# fngAfro.net
KiCad netlist of a schematic drawn in EAGLE
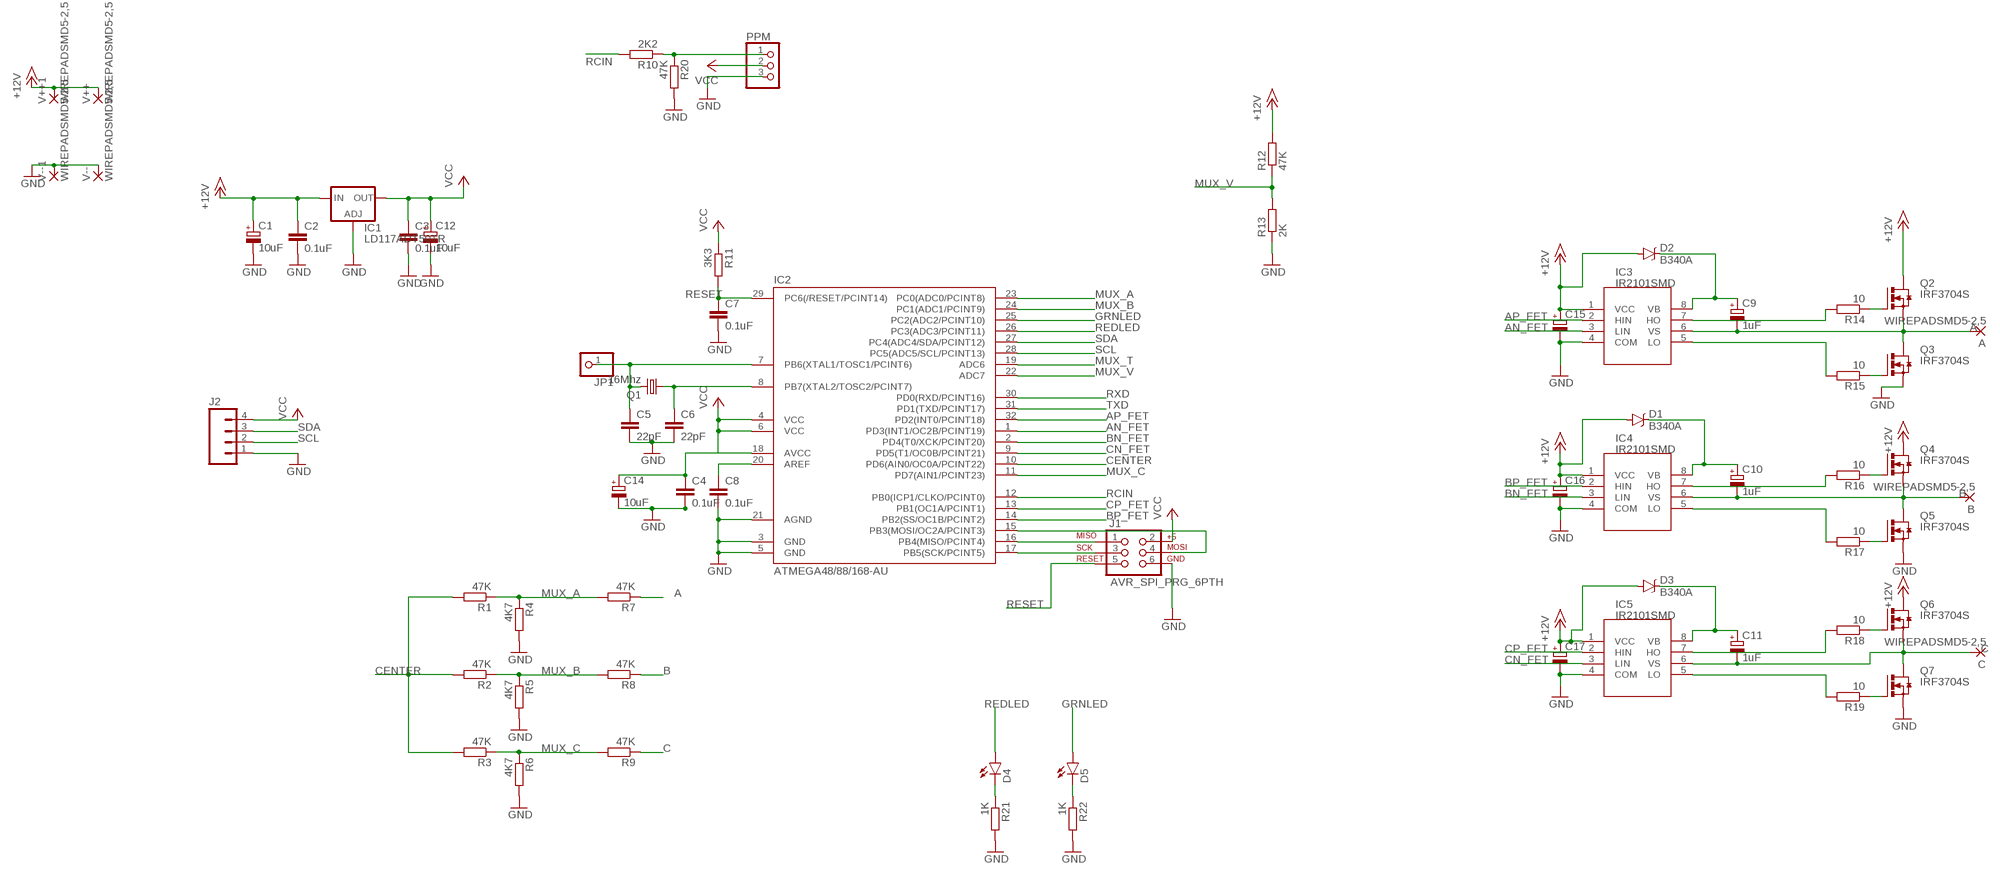
[diagram p0: schematic, sheet 1]

(export (version "E")
  (design (tool "Eeschema 10.0.6"))
  (components
    (comp (ref "A")
      (value "WIREPADSMD5-2,5")
      (footprint "eagle-import:5-2,5")
      (libsource (lib "eagle-import") (part "WIREPADSMD5-2,5"))
    )
    (comp (ref "B")
      (value "WIREPADSMD5-2,5")
      (footprint "eagle-import:5-2,5")
      (libsource (lib "eagle-import") (part "WIREPADSMD5-2,5"))
    )
    (comp (ref "C")
      (value "WIREPADSMD5-2,5")
      (footprint "eagle-import:5-2,5")
      (libsource (lib "eagle-import") (part "WIREPADSMD5-2,5"))
    )
    (comp (ref "C1")
      (value "10uF")
      (footprint "eagle-import:CT3216")
      (libsource (lib "eagle-import") (part "CPOL-EUCT3216"))
    )
    (comp (ref "C2")
      (value "0.1uF")
      (footprint "eagle-import:C1206K")
      (libsource (lib "eagle-import") (part "C-EUC1206K"))
    )
    (comp (ref "C3")
      (value "0.1uF")
      (footprint "eagle-import:C1206K")
      (libsource (lib "eagle-import") (part "C-EUC1206K"))
    )
    (comp (ref "C4")
      (value "0.1uF")
      (footprint "eagle-import:C1206K")
      (libsource (lib "eagle-import") (part "C-EUC1206K"))
    )
    (comp (ref "C5")
      (value "22pF")
      (footprint "eagle-import:C1206K")
      (libsource (lib "eagle-import") (part "C-EUC1206K"))
    )
    (comp (ref "C6")
      (value "22pF")
      (footprint "eagle-import:C1206K")
      (libsource (lib "eagle-import") (part "C-EUC1206K"))
    )
    (comp (ref "C7")
      (value "0.1uF")
      (footprint "eagle-import:C1206K")
      (libsource (lib "eagle-import") (part "C-EUC1206K"))
    )
    (comp (ref "C8")
      (value "0.1uF")
      (footprint "eagle-import:C1206K")
      (libsource (lib "eagle-import") (part "C-EUC1206K"))
    )
    (comp (ref "C9")
      (value "1uF")
      (footprint "eagle-import:B_3528-21R")
      (libsource (lib "eagle-import") (part "CPOL-EUB/3528-21R"))
    )
    (comp (ref "C10")
      (value "1uF")
      (footprint "eagle-import:B_3528-21R")
      (libsource (lib "eagle-import") (part "CPOL-EUB/3528-21R"))
    )
    (comp (ref "C11")
      (value "1uF")
      (footprint "eagle-import:B_3528-21R")
      (libsource (lib "eagle-import") (part "CPOL-EUB/3528-21R"))
    )
    (comp (ref "C12")
      (value "10uF")
      (footprint "eagle-import:A_3216-18W")
      (libsource (lib "eagle-import") (part "CPOL-EUA/3216-18W"))
    )
    (comp (ref "C14")
      (value "10uF")
      (footprint "eagle-import:A_3216-18W")
      (libsource (lib "eagle-import") (part "CPOL-EUA/3216-18W"))
    )
    (comp (ref "C15")
      (value "CPOL-EUA/3216-18W")
      (footprint "eagle-import:A_3216-18W")
      (libsource (lib "eagle-import") (part "CPOL-EUA/3216-18W"))
    )
    (comp (ref "C16")
      (value "CPOL-EUA/3216-18W")
      (footprint "eagle-import:A_3216-18W")
      (libsource (lib "eagle-import") (part "CPOL-EUA/3216-18W"))
    )
    (comp (ref "C17")
      (value "CPOL-EUA/3216-18W")
      (footprint "eagle-import:A_3216-18W")
      (libsource (lib "eagle-import") (part "CPOL-EUA/3216-18W"))
    )
    (comp (ref "D1")
      (value "B340A")
      (footprint "eagle-import:SMA-DIODE")
      (libsource (lib "eagle-import") (part "DIODE-SCHOTTKY-B340A"))
    )
    (comp (ref "D2")
      (value "B340A")
      (footprint "eagle-import:SMA-DIODE")
      (libsource (lib "eagle-import") (part "DIODE-SCHOTTKY-B340A"))
    )
    (comp (ref "D3")
      (value "B340A")
      (footprint "eagle-import:SMA-DIODE")
      (libsource (lib "eagle-import") (part "DIODE-SCHOTTKY-B340A"))
    )
    (comp (ref "D4")
      (value "LED-FKIT-1206")
      (footprint "eagle-import:FKIT-LED-1206")
      (libsource (lib "eagle-import") (part "LED-FKIT-1206"))
    )
    (comp (ref "D5")
      (value "LED-FKIT-1206")
      (footprint "eagle-import:FKIT-LED-1206")
      (libsource (lib "eagle-import") (part "LED-FKIT-1206"))
    )
    (comp (ref "IC1")
      (value "LD117ADT50TR")
      (footprint "eagle-import:DPACK")
      (libsource (lib "eagle-import") (part "LD117A?DT50TR"))
    )
    (comp (ref "IC2")
      (value "ATMEGA48/88/168-AU")
      (footprint "eagle-import:TQFP32-08")
      (libsource (lib "eagle-import") (part "ATMEGA48/88/168-AU"))
    )
    (comp (ref "IC3")
      (value "IR2101SMD")
      (footprint "eagle-import:SO08")
      (libsource (lib "eagle-import") (part "IR2101SMD"))
    )
    (comp (ref "IC4")
      (value "IR2101SMD")
      (footprint "eagle-import:SO08")
      (libsource (lib "eagle-import") (part "IR2101SMD"))
    )
    (comp (ref "IC5")
      (value "IR2101SMD")
      (footprint "eagle-import:SO08")
      (libsource (lib "eagle-import") (part "IR2101SMD"))
    )
    (comp (ref "J1")
      (value "AVR_SPI_PRG_6PTH")
      (footprint "eagle-import:2X3")
      (libsource (lib "eagle-import") (part "AVR_SPI_PRG_6PTH"))
    )
    (comp (ref "J2")
      (value "M04LOCK")
      (footprint "eagle-import:1X04_LOCK")
      (libsource (lib "eagle-import") (part "M04LOCK"))
    )
    (comp (ref "JP1")
      (value "PINHD-1X1")
      (footprint "eagle-import:1X01")
      (libsource (lib "eagle-import") (part "PINHD-1X1"))
    )
    (comp (ref "PPM")
      (value "PINHD-1X3/90")
      (footprint "eagle-import:1X03_90")
      (libsource (lib "eagle-import") (part "PINHD-1X3/90"))
    )
    (comp (ref "Q1")
      (value "16Mhz")
      (footprint "eagle-import:HC49U70")
      (libsource (lib "eagle-import") (part "CRYSTALHC49U70"))
    )
    (comp (ref "Q2")
      (value "IRF3704S")
      (footprint "eagle-import:D2PACK")
      (libsource (lib "eagle-import") (part "IRF3704S"))
    )
    (comp (ref "Q3")
      (value "IRF3704S")
      (footprint "eagle-import:D2PACK")
      (libsource (lib "eagle-import") (part "IRF3704S"))
    )
    (comp (ref "Q4")
      (value "IRF3704S")
      (footprint "eagle-import:D2PACK")
      (libsource (lib "eagle-import") (part "IRF3704S"))
    )
    (comp (ref "Q5")
      (value "IRF3704S")
      (footprint "eagle-import:D2PACK")
      (libsource (lib "eagle-import") (part "IRF3704S"))
    )
    (comp (ref "Q6")
      (value "IRF3704S")
      (footprint "eagle-import:D2PACK")
      (libsource (lib "eagle-import") (part "IRF3704S"))
    )
    (comp (ref "Q7")
      (value "IRF3704S")
      (footprint "eagle-import:D2PACK")
      (libsource (lib "eagle-import") (part "IRF3704S"))
    )
    (comp (ref "R1")
      (value "47K")
      (footprint "eagle-import:M0805")
      (libsource (lib "eagle-import") (part "R-EU_M0805"))
    )
    (comp (ref "R2")
      (value "47K")
      (footprint "eagle-import:M0805")
      (libsource (lib "eagle-import") (part "R-EU_M0805"))
    )
    (comp (ref "R3")
      (value "47K")
      (footprint "eagle-import:M0805")
      (libsource (lib "eagle-import") (part "R-EU_M0805"))
    )
    (comp (ref "R4")
      (value "4K7")
      (footprint "eagle-import:M0805")
      (libsource (lib "eagle-import") (part "R-EU_M0805"))
    )
    (comp (ref "R5")
      (value "4K7")
      (footprint "eagle-import:M0805")
      (libsource (lib "eagle-import") (part "R-EU_M0805"))
    )
    (comp (ref "R6")
      (value "4K7")
      (footprint "eagle-import:M0805")
      (libsource (lib "eagle-import") (part "R-EU_M0805"))
    )
    (comp (ref "R7")
      (value "47K")
      (footprint "eagle-import:M0805")
      (libsource (lib "eagle-import") (part "R-EU_M0805"))
    )
    (comp (ref "R8")
      (value "47K")
      (footprint "eagle-import:M0805")
      (libsource (lib "eagle-import") (part "R-EU_M0805"))
    )
    (comp (ref "R9")
      (value "47K")
      (footprint "eagle-import:M0805")
      (libsource (lib "eagle-import") (part "R-EU_M0805"))
    )
    (comp (ref "R10")
      (value "2K2")
      (footprint "eagle-import:M1206")
      (libsource (lib "eagle-import") (part "R-EU_M1206"))
    )
    (comp (ref "R11")
      (value "3K3")
      (footprint "eagle-import:M1206")
      (libsource (lib "eagle-import") (part "R-EU_M1206"))
    )
    (comp (ref "R12")
      (value "47K")
      (footprint "eagle-import:M0805")
      (libsource (lib "eagle-import") (part "R-EU_M0805"))
    )
    (comp (ref "R13")
      (value "2K")
      (footprint "eagle-import:M0805")
      (libsource (lib "eagle-import") (part "R-EU_M0805"))
    )
    (comp (ref "R14")
      (value "10")
      (footprint "eagle-import:M0805")
      (libsource (lib "eagle-import") (part "R-EU_M0805"))
    )
    (comp (ref "R15")
      (value "10")
      (footprint "eagle-import:M0805")
      (libsource (lib "eagle-import") (part "R-EU_M0805"))
    )
    (comp (ref "R16")
      (value "10")
      (footprint "eagle-import:M0805")
      (libsource (lib "eagle-import") (part "R-EU_M0805"))
    )
    (comp (ref "R17")
      (value "10")
      (footprint "eagle-import:M0805")
      (libsource (lib "eagle-import") (part "R-EU_M0805"))
    )
    (comp (ref "R18")
      (value "10")
      (footprint "eagle-import:M0805")
      (libsource (lib "eagle-import") (part "R-EU_M0805"))
    )
    (comp (ref "R19")
      (value "10")
      (footprint "eagle-import:M0805")
      (libsource (lib "eagle-import") (part "R-EU_M0805"))
    )
    (comp (ref "R20")
      (value "47K")
      (footprint "eagle-import:M1206")
      (libsource (lib "eagle-import") (part "R-EU_M1206"))
    )
    (comp (ref "R21")
      (value "1K")
      (footprint "eagle-import:M0805")
      (libsource (lib "eagle-import") (part "R-EU_M0805"))
    )
    (comp (ref "R22")
      (value "1K")
      (footprint "eagle-import:M0805")
      (libsource (lib "eagle-import") (part "R-EU_M0805"))
    )
    (comp (ref "V++")
      (value "WIREPADSMD5-2,5")
      (footprint "eagle-import:5-2,5")
      (libsource (lib "eagle-import") (part "WIREPADSMD5-2,5"))
    )
    (comp (ref "V++1")
      (value "WIREPADSMD5-2,5")
      (footprint "eagle-import:5-2,5")
      (libsource (lib "eagle-import") (part "WIREPADSMD5-2,5"))
    )
    (comp (ref "V--")
      (value "WIREPADSMD5-2,5")
      (footprint "eagle-import:5-2,5")
      (libsource (lib "eagle-import") (part "WIREPADSMD5-2,5"))
    )
    (comp (ref "V--1")
      (value "WIREPADSMD5-2,5")
      (footprint "eagle-import:5-2,5")
      (libsource (lib "eagle-import") (part "WIREPADSMD5-2,5"))
    )
  )
  (nets
    (net (code "1") (name "+12V") (class "Default")
      (node (ref "C1") (pin "+") (pinfunction "+_+") (pintype "passive"))
      (node (ref "C15") (pin "+") (pinfunction "+_+") (pintype "passive"))
      (node (ref "C16") (pin "+") (pinfunction "+_+") (pintype "passive"))
      (node (ref "C17") (pin "+") (pinfunction "+_+") (pintype "passive"))
      (node (ref "C2") (pin "1") (pinfunction "1_1") (pintype "passive"))
      (node (ref "D1") (pin "A") (pinfunction "A_A") (pintype "passive"))
      (node (ref "D2") (pin "A") (pinfunction "A_A") (pintype "passive"))
      (node (ref "D3") (pin "A") (pinfunction "A_A") (pintype "passive"))
      (node (ref "IC1") (pin "3") (pinfunction "IN_3") (pintype "input"))
      (node (ref "IC3") (pin "1") (pinfunction "VCC_1") (pintype "bidirectional"))
      (node (ref "IC4") (pin "1") (pinfunction "VCC_1") (pintype "bidirectional"))
      (node (ref "IC5") (pin "1") (pinfunction "VCC_1") (pintype "bidirectional"))
      (node (ref "Q2") (pin "2") (pinfunction "D_2") (pintype "passive"))
      (node (ref "Q4") (pin "2") (pinfunction "D_2") (pintype "passive"))
      (node (ref "Q6") (pin "2") (pinfunction "D_2") (pintype "passive"))
      (node (ref "R12") (pin "2") (pinfunction "2_2") (pintype "passive"))
      (node (ref "V++") (pin "1") (pinfunction "P_1") (pintype "passive"))
      (node (ref "V++1") (pin "1") (pinfunction "P_1") (pintype "passive"))
    )
    (net (code "2") (name "/A") (class "Default")
      (node (ref "A") (pin "1") (pinfunction "P_1") (pintype "passive"))
      (node (ref "C9") (pin "-") (pinfunction "-_-") (pintype "passive"))
      (node (ref "IC3") (pin "6") (pinfunction "VS_6") (pintype "bidirectional"))
      (node (ref "Q2") (pin "3") (pinfunction "S_3") (pintype "passive"))
      (node (ref "Q3") (pin "2") (pinfunction "D_2") (pintype "passive"))
      (node (ref "R7") (pin "1") (pinfunction "1_1") (pintype "passive"))
    )
    (net (code "3") (name "/AN_FET") (class "Default")
      (node (ref "IC2") (pin "1") (pinfunction "PD3(INT1/OC2B/PCINT19)_1") (pintype "bidirectional"))
      (node (ref "IC3") (pin "3") (pinfunction "LIN_3") (pintype "bidirectional"))
    )
    (net (code "4") (name "/AP_FET") (class "Default")
      (node (ref "IC2") (pin "32") (pinfunction "PD2(INT0/PCINT18)_32") (pintype "bidirectional"))
      (node (ref "IC3") (pin "2") (pinfunction "HIN_2") (pintype "bidirectional"))
    )
    (net (code "5") (name "/B") (class "Default")
      (node (ref "B") (pin "1") (pinfunction "P_1") (pintype "passive"))
      (node (ref "C10") (pin "-") (pinfunction "-_-") (pintype "passive"))
      (node (ref "IC4") (pin "6") (pinfunction "VS_6") (pintype "bidirectional"))
      (node (ref "Q4") (pin "3") (pinfunction "S_3") (pintype "passive"))
      (node (ref "Q5") (pin "2") (pinfunction "D_2") (pintype "passive"))
      (node (ref "R8") (pin "1") (pinfunction "1_1") (pintype "passive"))
    )
    (net (code "6") (name "/BN_FET") (class "Default")
      (node (ref "IC2") (pin "2") (pinfunction "PD4(T0/XCK/PCINT20)_2") (pintype "bidirectional"))
      (node (ref "IC4") (pin "3") (pinfunction "LIN_3") (pintype "bidirectional"))
    )
    (net (code "7") (name "/BP_FET") (class "Default")
      (node (ref "IC2") (pin "14") (pinfunction "PB2(SS/OC1B/PCINT2)_14") (pintype "bidirectional"))
      (node (ref "IC4") (pin "2") (pinfunction "HIN_2") (pintype "bidirectional"))
    )
    (net (code "8") (name "/C") (class "Default")
      (node (ref "C") (pin "1") (pinfunction "P_1") (pintype "passive"))
      (node (ref "C11") (pin "-") (pinfunction "-_-") (pintype "passive"))
      (node (ref "IC5") (pin "6") (pinfunction "VS_6") (pintype "bidirectional"))
      (node (ref "Q6") (pin "3") (pinfunction "S_3") (pintype "passive"))
      (node (ref "Q7") (pin "2") (pinfunction "D_2") (pintype "passive"))
      (node (ref "R9") (pin "1") (pinfunction "1_1") (pintype "passive"))
    )
    (net (code "9") (name "/CENTER") (class "Default")
      (node (ref "IC2") (pin "10") (pinfunction "PD6(AIN0/OC0A/PCINT22)_10") (pintype "bidirectional"))
      (node (ref "R1") (pin "2") (pinfunction "2_2") (pintype "passive"))
      (node (ref "R2") (pin "2") (pinfunction "2_2") (pintype "passive"))
      (node (ref "R3") (pin "2") (pinfunction "2_2") (pintype "passive"))
    )
    (net (code "10") (name "/CN_FET") (class "Default")
      (node (ref "IC2") (pin "9") (pinfunction "PD5(T1/OC0B/PCINT21)_9") (pintype "bidirectional"))
      (node (ref "IC5") (pin "3") (pinfunction "LIN_3") (pintype "bidirectional"))
    )
    (net (code "11") (name "/CP_FET") (class "Default")
      (node (ref "IC2") (pin "13") (pinfunction "PB1(OC1A/PCINT1)_13") (pintype "bidirectional"))
      (node (ref "IC5") (pin "2") (pinfunction "HIN_2") (pintype "bidirectional"))
    )
    (net (code "12") (name "/GRNLED") (class "Default")
      (node (ref "D5") (pin "A") (pinfunction "A_A") (pintype "passive"))
      (node (ref "IC2") (pin "25") (pinfunction "PC2(ADC2/PCINT10)_25") (pintype "bidirectional"))
    )
    (net (code "13") (name "/MUX_A") (class "Default")
      (node (ref "IC2") (pin "23") (pinfunction "PC0(ADC0/PCINT8)_23") (pintype "bidirectional"))
      (node (ref "R1") (pin "1") (pinfunction "1_1") (pintype "passive"))
      (node (ref "R4") (pin "1") (pinfunction "1_1") (pintype "passive"))
      (node (ref "R7") (pin "2") (pinfunction "2_2") (pintype "passive"))
    )
    (net (code "14") (name "/MUX_B") (class "Default")
      (node (ref "IC2") (pin "24") (pinfunction "PC1(ADC1/PCINT9)_24") (pintype "bidirectional"))
      (node (ref "R2") (pin "1") (pinfunction "1_1") (pintype "passive"))
      (node (ref "R5") (pin "1") (pinfunction "1_1") (pintype "passive"))
      (node (ref "R8") (pin "2") (pinfunction "2_2") (pintype "passive"))
    )
    (net (code "15") (name "/MUX_C") (class "Default")
      (node (ref "IC2") (pin "11") (pinfunction "PD7(AIN1/PCINT23)_11") (pintype "bidirectional"))
      (node (ref "R3") (pin "1") (pinfunction "1_1") (pintype "passive"))
      (node (ref "R6") (pin "1") (pinfunction "1_1") (pintype "passive"))
      (node (ref "R9") (pin "2") (pinfunction "2_2") (pintype "passive"))
    )
    (net (code "16") (name "/MUX_T") (class "Default")
      (node (ref "IC2") (pin "19") (pinfunction "ADC6_19") (pintype "passive"))
    )
    (net (code "17") (name "/MUX_V") (class "Default")
      (node (ref "IC2") (pin "22") (pinfunction "ADC7_22") (pintype "passive"))
      (node (ref "R12") (pin "1") (pinfunction "1_1") (pintype "passive"))
      (node (ref "R13") (pin "2") (pinfunction "2_2") (pintype "passive"))
    )
    (net (code "18") (name "/RCIN") (class "Default")
      (node (ref "IC2") (pin "12") (pinfunction "PB0(ICP1/CLKO/PCINT0)_12") (pintype "bidirectional"))
      (node (ref "R10") (pin "2") (pinfunction "2_2") (pintype "passive"))
    )
    (net (code "19") (name "/REDLED") (class "Default")
      (node (ref "D4") (pin "A") (pinfunction "A_A") (pintype "passive"))
      (node (ref "IC2") (pin "26") (pinfunction "PC3(ADC3/PCINT11)_26") (pintype "bidirectional"))
    )
    (net (code "20") (name "/RESET") (class "Default")
      (node (ref "C7") (pin "1") (pinfunction "1_1") (pintype "passive"))
      (node (ref "IC2") (pin "29") (pinfunction "PC6(/RESET/PCINT14)_29") (pintype "bidirectional"))
      (node (ref "J1") (pin "5") (pinfunction "5_5") (pintype "passive"))
      (node (ref "R11") (pin "2") (pinfunction "2_2") (pintype "passive"))
    )
    (net (code "21") (name "/RXD") (class "Default")
      (node (ref "IC2") (pin "30") (pinfunction "PD0(RXD/PCINT16)_30") (pintype "bidirectional"))
    )
    (net (code "22") (name "/SCL") (class "Default")
      (node (ref "IC2") (pin "28") (pinfunction "PC5(ADC5/SCL/PCINT13)_28") (pintype "bidirectional"))
      (node (ref "J2") (pin "2") (pinfunction "2_2") (pintype "passive"))
    )
    (net (code "23") (name "/SDA") (class "Default")
      (node (ref "IC2") (pin "27") (pinfunction "PC4(ADC4/SDA/PCINT12)_27") (pintype "bidirectional"))
      (node (ref "J2") (pin "3") (pinfunction "3_3") (pintype "passive"))
    )
    (net (code "24") (name "/TXD") (class "Default")
      (node (ref "IC2") (pin "31") (pinfunction "PD1(TXD/PCINT17)_31") (pintype "bidirectional"))
    )
    (net (code "25") (name "GND") (class "Default")
      (node (ref "C1") (pin "-") (pinfunction "-_-") (pintype "passive"))
      (node (ref "C12") (pin "-") (pinfunction "-_-") (pintype "passive"))
      (node (ref "C14") (pin "-") (pinfunction "-_-") (pintype "passive"))
      (node (ref "C15") (pin "-") (pinfunction "-_-") (pintype "passive"))
      (node (ref "C16") (pin "-") (pinfunction "-_-") (pintype "passive"))
      (node (ref "C17") (pin "-") (pinfunction "-_-") (pintype "passive"))
      (node (ref "C2") (pin "2") (pinfunction "2_2") (pintype "passive"))
      (node (ref "C3") (pin "2") (pinfunction "2_2") (pintype "passive"))
      (node (ref "C4") (pin "2") (pinfunction "2_2") (pintype "passive"))
      (node (ref "C5") (pin "2") (pinfunction "2_2") (pintype "passive"))
      (node (ref "C6") (pin "2") (pinfunction "2_2") (pintype "passive"))
      (node (ref "C7") (pin "2") (pinfunction "2_2") (pintype "passive"))
      (node (ref "C8") (pin "2") (pinfunction "2_2") (pintype "passive"))
      (node (ref "IC1") (pin "1") (pinfunction "ADJ_1") (pintype "input"))
      (node (ref "IC2") (pin "21") (pinfunction "AGND_21") (pintype "power_in"))
      (node (ref "IC2") (pin "3") (pinfunction "GND_3") (pintype "power_in"))
      (node (ref "IC2") (pin "5") (pinfunction "GND_5") (pintype "power_in"))
      (node (ref "IC3") (pin "4") (pinfunction "COM_4") (pintype "bidirectional"))
      (node (ref "IC4") (pin "4") (pinfunction "COM_4") (pintype "bidirectional"))
      (node (ref "IC5") (pin "4") (pinfunction "COM_4") (pintype "bidirectional"))
      (node (ref "J1") (pin "6") (pinfunction "6_6") (pintype "passive"))
      (node (ref "J2") (pin "1") (pinfunction "1_1") (pintype "passive"))
      (node (ref "PPM") (pin "3") (pinfunction "3_3") (pintype "passive"))
      (node (ref "Q3") (pin "3") (pinfunction "S_3") (pintype "passive"))
      (node (ref "Q5") (pin "3") (pinfunction "S_3") (pintype "passive"))
      (node (ref "Q7") (pin "3") (pinfunction "S_3") (pintype "passive"))
      (node (ref "R13") (pin "1") (pinfunction "1_1") (pintype "passive"))
      (node (ref "R20") (pin "2") (pinfunction "2_2") (pintype "passive"))
      (node (ref "R21") (pin "2") (pinfunction "2_2") (pintype "passive"))
      (node (ref "R22") (pin "2") (pinfunction "2_2") (pintype "passive"))
      (node (ref "R4") (pin "2") (pinfunction "2_2") (pintype "passive"))
      (node (ref "R5") (pin "2") (pinfunction "2_2") (pintype "passive"))
      (node (ref "R6") (pin "2") (pinfunction "2_2") (pintype "passive"))
      (node (ref "V--") (pin "1") (pinfunction "P_1") (pintype "passive"))
      (node (ref "V--1") (pin "1") (pinfunction "P_1") (pintype "passive"))
    )
    (net (code "26") (name "Net-(D4-PadC)") (class "Default")
      (node (ref "D4") (pin "C") (pinfunction "C_C") (pintype "passive"))
      (node (ref "R21") (pin "1") (pinfunction "1_1") (pintype "passive"))
    )
    (net (code "27") (name "Net-(D5-PadC)") (class "Default")
      (node (ref "D5") (pin "C") (pinfunction "C_C") (pintype "passive"))
      (node (ref "R22") (pin "1") (pinfunction "1_1") (pintype "passive"))
    )
    (net (code "28") (name "Net-(IC2-AREF)") (class "Default")
      (node (ref "C8") (pin "1") (pinfunction "1_1") (pintype "passive"))
      (node (ref "IC2") (pin "20") (pinfunction "AREF_20") (pintype "passive"))
    )
    (net (code "29") (name "Net-(IC2-PB3(MOSI{slash}OC2A{slash}PCINT3))") (class "Default")
      (node (ref "IC2") (pin "15") (pinfunction "PB3(MOSI/OC2A/PCINT3)_15") (pintype "bidirectional"))
      (node (ref "J1") (pin "4") (pinfunction "4_4") (pintype "passive"))
    )
    (net (code "30") (name "Net-(IC2-PB4(MISO{slash}PCINT4))") (class "Default")
      (node (ref "IC2") (pin "16") (pinfunction "PB4(MISO/PCINT4)_16") (pintype "bidirectional"))
      (node (ref "J1") (pin "1") (pinfunction "1_1") (pintype "passive"))
    )
    (net (code "31") (name "Net-(IC2-PB5(SCK{slash}PCINT5))") (class "Default")
      (node (ref "IC2") (pin "17") (pinfunction "PB5(SCK/PCINT5)_17") (pintype "bidirectional"))
      (node (ref "J1") (pin "3") (pinfunction "3_3") (pintype "passive"))
    )
    (net (code "32") (name "Net-(IC2-PB6(XTAL1{slash}TOSC1{slash}PCINT6))") (class "Default")
      (node (ref "C5") (pin "1") (pinfunction "1_1") (pintype "passive"))
      (node (ref "IC2") (pin "7") (pinfunction "PB6(XTAL1/TOSC1/PCINT6)_7") (pintype "bidirectional"))
      (node (ref "JP1") (pin "1") (pinfunction "1_1") (pintype "passive"))
      (node (ref "Q1") (pin "2") (pinfunction "2_2") (pintype "passive"))
    )
    (net (code "33") (name "Net-(IC2-PB7(XTAL2{slash}TOSC2{slash}PCINT7))") (class "Default")
      (node (ref "C6") (pin "1") (pinfunction "1_1") (pintype "passive"))
      (node (ref "IC2") (pin "8") (pinfunction "PB7(XTAL2/TOSC2/PCINT7)_8") (pintype "bidirectional"))
      (node (ref "Q1") (pin "1") (pinfunction "1_1") (pintype "passive"))
    )
    (net (code "34") (name "Net-(IC3-HO)") (class "Default")
      (node (ref "IC3") (pin "7") (pinfunction "HO_7") (pintype "bidirectional"))
      (node (ref "R14") (pin "2") (pinfunction "2_2") (pintype "passive"))
    )
    (net (code "35") (name "Net-(IC3-LO)") (class "Default")
      (node (ref "IC3") (pin "5") (pinfunction "LO_5") (pintype "bidirectional"))
      (node (ref "R15") (pin "2") (pinfunction "2_2") (pintype "passive"))
    )
    (net (code "36") (name "Net-(IC3-VB)") (class "Default")
      (node (ref "C9") (pin "+") (pinfunction "+_+") (pintype "passive"))
      (node (ref "D2") (pin "C") (pinfunction "C_C") (pintype "passive"))
      (node (ref "IC3") (pin "8") (pinfunction "VB_8") (pintype "bidirectional"))
    )
    (net (code "37") (name "Net-(IC4-HO)") (class "Default")
      (node (ref "IC4") (pin "7") (pinfunction "HO_7") (pintype "bidirectional"))
      (node (ref "R16") (pin "2") (pinfunction "2_2") (pintype "passive"))
    )
    (net (code "38") (name "Net-(IC4-LO)") (class "Default")
      (node (ref "IC4") (pin "5") (pinfunction "LO_5") (pintype "bidirectional"))
      (node (ref "R17") (pin "2") (pinfunction "2_2") (pintype "passive"))
    )
    (net (code "39") (name "Net-(IC4-VB)") (class "Default")
      (node (ref "C10") (pin "+") (pinfunction "+_+") (pintype "passive"))
      (node (ref "D1") (pin "C") (pinfunction "C_C") (pintype "passive"))
      (node (ref "IC4") (pin "8") (pinfunction "VB_8") (pintype "bidirectional"))
    )
    (net (code "40") (name "Net-(IC5-HO)") (class "Default")
      (node (ref "IC5") (pin "7") (pinfunction "HO_7") (pintype "bidirectional"))
      (node (ref "R18") (pin "2") (pinfunction "2_2") (pintype "passive"))
    )
    (net (code "41") (name "Net-(IC5-LO)") (class "Default")
      (node (ref "IC5") (pin "5") (pinfunction "LO_5") (pintype "bidirectional"))
      (node (ref "R19") (pin "2") (pinfunction "2_2") (pintype "passive"))
    )
    (net (code "42") (name "Net-(IC5-VB)") (class "Default")
      (node (ref "C11") (pin "+") (pinfunction "+_+") (pintype "passive"))
      (node (ref "D3") (pin "C") (pinfunction "C_C") (pintype "passive"))
      (node (ref "IC5") (pin "8") (pinfunction "VB_8") (pintype "bidirectional"))
    )
    (net (code "43") (name "Net-(PPM-Pad1)") (class "Default")
      (node (ref "PPM") (pin "1") (pinfunction "1_1") (pintype "passive"))
      (node (ref "R10") (pin "1") (pinfunction "1_1") (pintype "passive"))
      (node (ref "R20") (pin "1") (pinfunction "1_1") (pintype "passive"))
    )
    (net (code "44") (name "Net-(Q2-G)") (class "Default")
      (node (ref "Q2") (pin "1") (pinfunction "G_1") (pintype "passive"))
      (node (ref "R14") (pin "1") (pinfunction "1_1") (pintype "passive"))
    )
    (net (code "45") (name "Net-(Q3-G)") (class "Default")
      (node (ref "Q3") (pin "1") (pinfunction "G_1") (pintype "passive"))
      (node (ref "R15") (pin "1") (pinfunction "1_1") (pintype "passive"))
    )
    (net (code "46") (name "Net-(Q4-G)") (class "Default")
      (node (ref "Q4") (pin "1") (pinfunction "G_1") (pintype "passive"))
      (node (ref "R16") (pin "1") (pinfunction "1_1") (pintype "passive"))
    )
    (net (code "47") (name "Net-(Q5-G)") (class "Default")
      (node (ref "Q5") (pin "1") (pinfunction "G_1") (pintype "passive"))
      (node (ref "R17") (pin "1") (pinfunction "1_1") (pintype "passive"))
    )
    (net (code "48") (name "Net-(Q6-G)") (class "Default")
      (node (ref "Q6") (pin "1") (pinfunction "G_1") (pintype "passive"))
      (node (ref "R18") (pin "1") (pinfunction "1_1") (pintype "passive"))
    )
    (net (code "49") (name "Net-(Q7-G)") (class "Default")
      (node (ref "Q7") (pin "1") (pinfunction "G_1") (pintype "passive"))
      (node (ref "R19") (pin "1") (pinfunction "1_1") (pintype "passive"))
    )
    (net (code "50") (name "VCC") (class "Default")
      (node (ref "C12") (pin "+") (pinfunction "+_+") (pintype "passive"))
      (node (ref "C14") (pin "+") (pinfunction "+_+") (pintype "passive"))
      (node (ref "C3") (pin "1") (pinfunction "1_1") (pintype "passive"))
      (node (ref "C4") (pin "1") (pinfunction "1_1") (pintype "passive"))
      (node (ref "IC1") (pin "4") (pinfunction "OUT_4") (pintype "passive"))
      (node (ref "IC2") (pin "18") (pinfunction "AVCC_18") (pintype "passive"))
      (node (ref "IC2") (pin "4") (pinfunction "VCC_4") (pintype "power_in"))
      (node (ref "IC2") (pin "6") (pinfunction "VCC_6") (pintype "power_in"))
      (node (ref "J1") (pin "2") (pinfunction "2_2") (pintype "passive"))
      (node (ref "J2") (pin "4") (pinfunction "4_4") (pintype "passive"))
      (node (ref "PPM") (pin "2") (pinfunction "2_2") (pintype "passive"))
      (node (ref "R11") (pin "1") (pinfunction "1_1") (pintype "passive"))
    )
  )
)
